# HMC2003_module_SET_RESET.net
KiCad netlist of a schematic drawn in Altium Designer
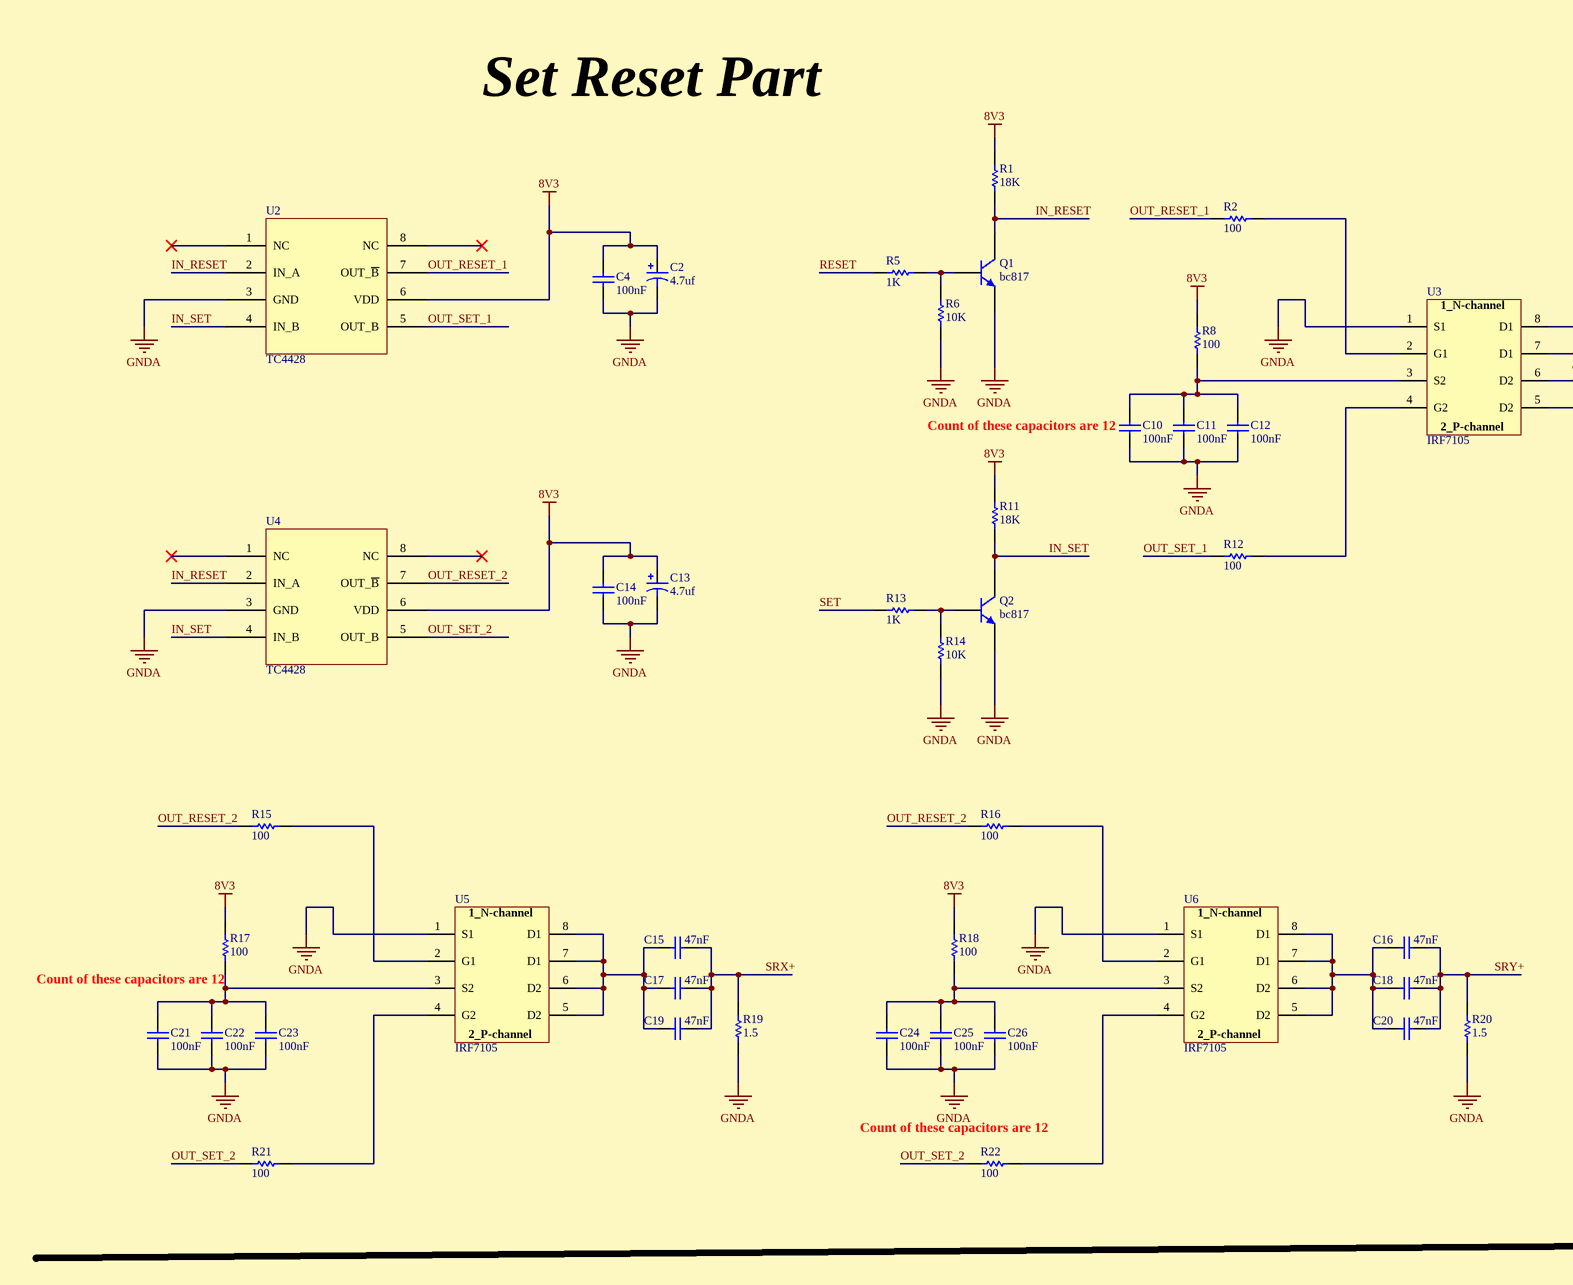
[diagram p0: HMC2003_module_SET_RESET.SchDoc, left]
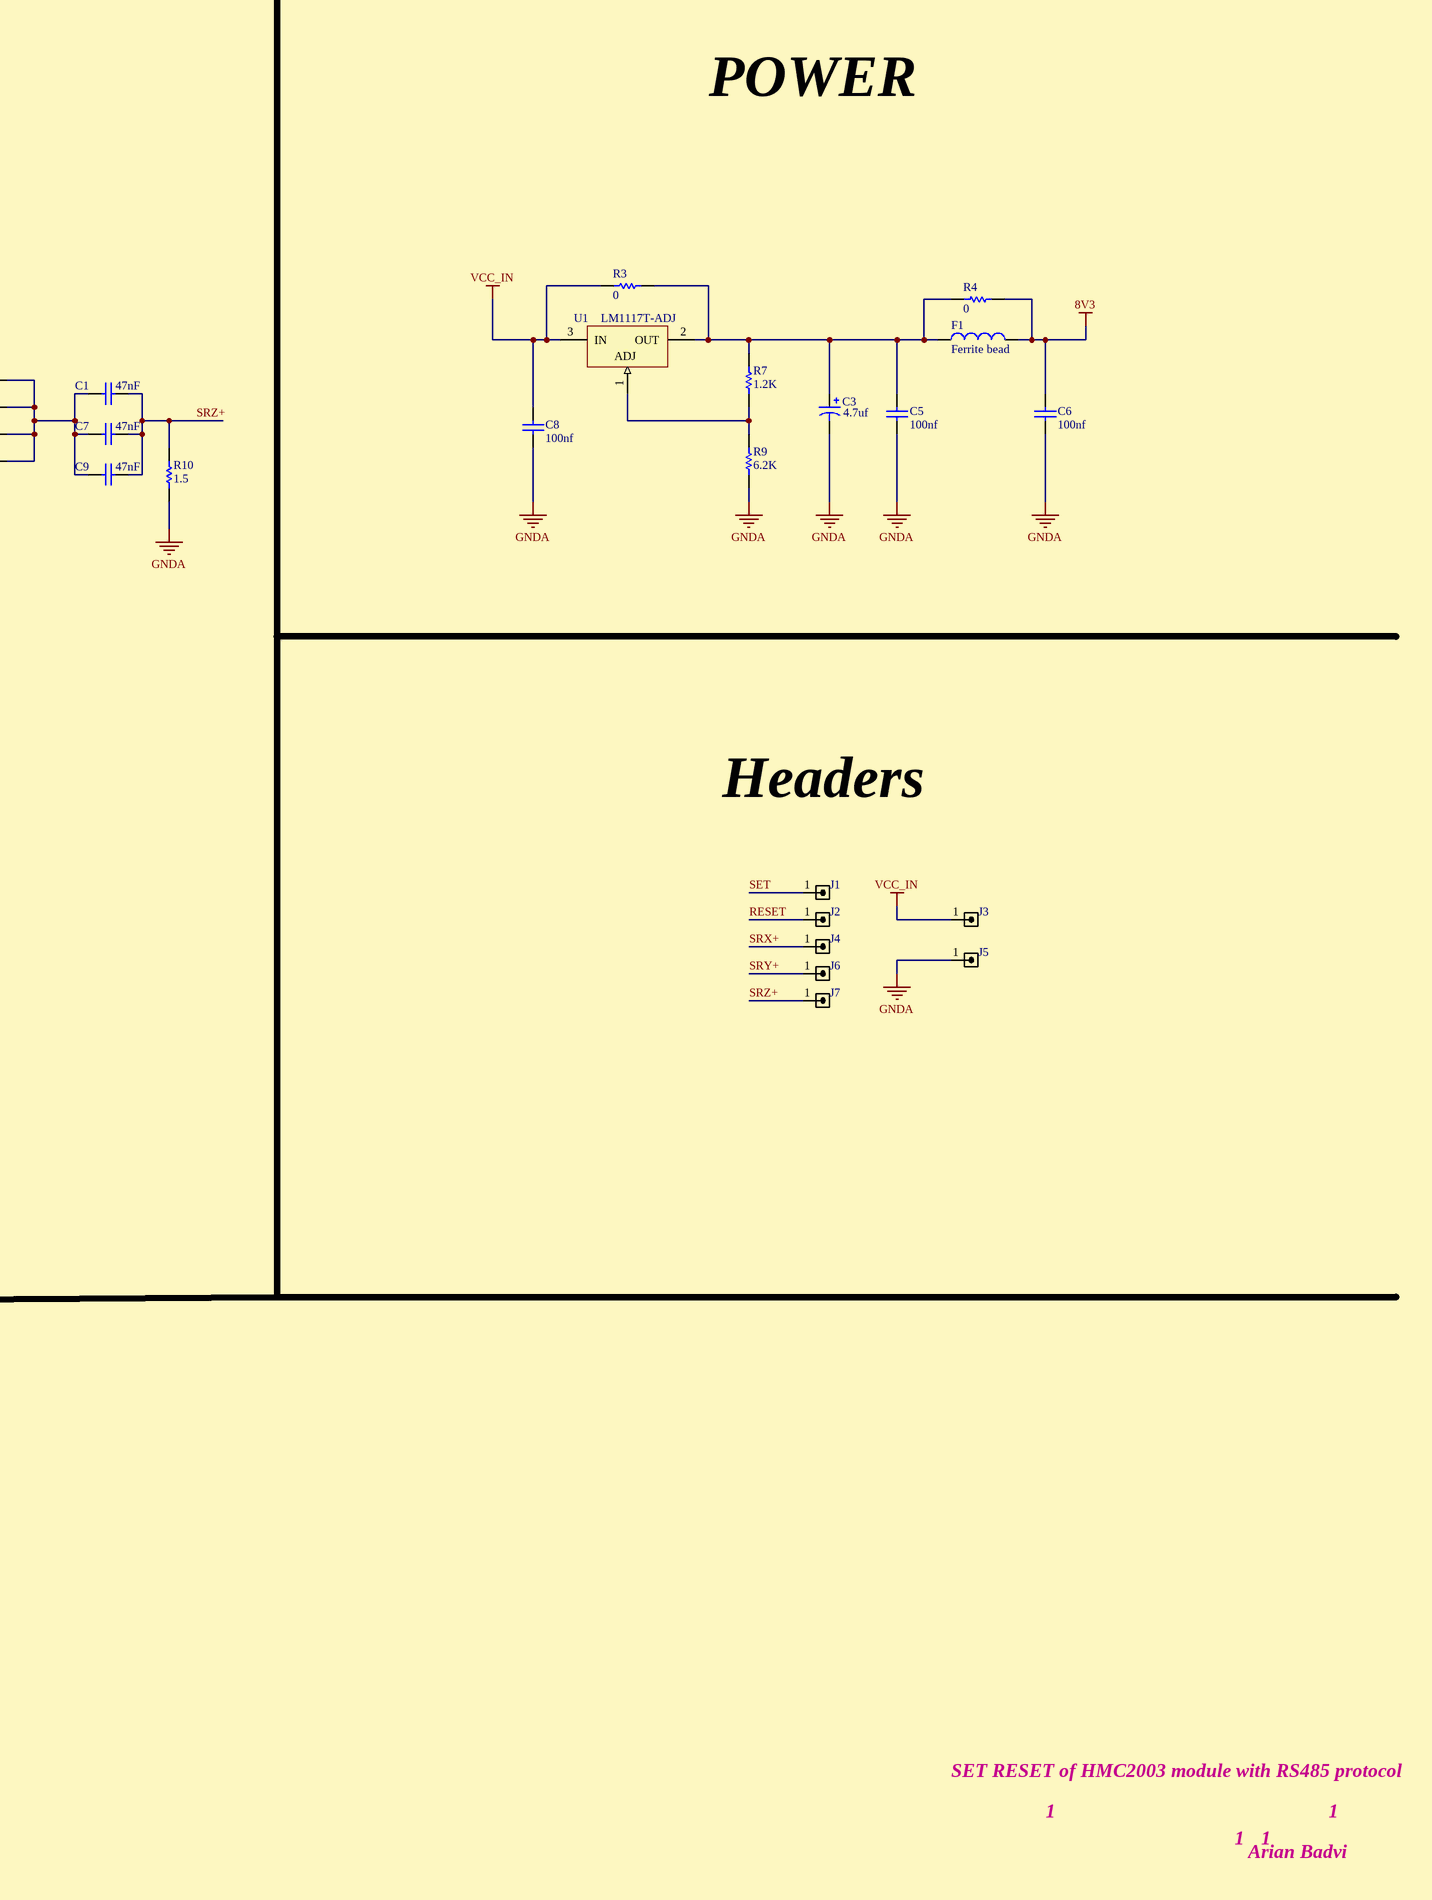
[diagram p1: HMC2003_module_SET_RESET.SchDoc, right]

(export (version "E")
  (design (tool "Eeschema 10.0.6"))
  (components
    (comp (ref "C1")
      (value "47nF")
      (footprint "C1206")
      (description "Capacitor")
      (fields (field (name "PUBLISHER") "Altium Limited"))
      (libsource (lib "Miscellaneous Devices") (part "Cap"))
    )
    (comp (ref "C2")
      (value "4.7uf")
      (footprint "cap_smd_a")
      (description "Polarized Capacitor (Radial)")
      (fields (field (name "PUBLISHER") "Altium Limited"))
      (libsource (lib "Miscellaneous Devices") (part "Cap Pol1"))
    )
    (comp (ref "C3")
      (value "4.7uf")
      (footprint "cap_smd_a")
      (description "Polarized Capacitor (Radial)")
      (fields (field (name "PUBLISHER") "Altium Limited"))
      (libsource (lib "") (part "Cap Pol1_1"))
    )
    (comp (ref "C4")
      (value "100nF")
      (footprint "C0805")
      (description "Capacitor")
      (fields (field (name "PUBLISHER") "Altium Limited"))
      (libsource (lib "") (part "Cap_1"))
    )
    (comp (ref "C5")
      (value "100nf")
      (footprint "C0805")
      (description "Capacitor")
      (fields (field (name "PUBLISHER") "Altium Limited"))
      (libsource (lib "") (part "Cap_1"))
    )
    (comp (ref "C6")
      (value "100nf")
      (footprint "C0805")
      (description "Capacitor")
      (fields (field (name "PUBLISHER") "Altium Limited"))
      (libsource (lib "") (part "Cap_1"))
    )
    (comp (ref "C7")
      (value "47nF")
      (footprint "C1206")
      (description "Capacitor")
      (fields (field (name "PUBLISHER") "Altium Limited"))
      (libsource (lib "Miscellaneous Devices") (part "Cap"))
    )
    (comp (ref "C8")
      (value "100nf")
      (footprint "C0805")
      (description "Capacitor")
      (fields (field (name "PUBLISHER") "Altium Limited"))
      (libsource (lib "") (part "Cap_1"))
    )
    (comp (ref "C9")
      (value "47nF")
      (footprint "C1206")
      (description "Capacitor")
      (fields (field (name "PUBLISHER") "Altium Limited"))
      (libsource (lib "Miscellaneous Devices") (part "Cap"))
    )
    (comp (ref "C10")
      (value "100nF")
      (footprint "C1206")
      (description "Capacitor")
      (fields (field (name "PUBLISHER") "Altium Limited"))
      (libsource (lib "") (part "Cap_1"))
    )
    (comp (ref "C11")
      (value "100nF")
      (footprint "C1206")
      (description "Capacitor")
      (fields (field (name "PUBLISHER") "Altium Limited"))
      (libsource (lib "") (part "Cap_1"))
    )
    (comp (ref "C12")
      (value "100nF")
      (footprint "C1206")
      (description "Capacitor")
      (fields (field (name "PUBLISHER") "Altium Limited"))
      (libsource (lib "") (part "Cap_1"))
    )
    (comp (ref "C13")
      (value "4.7uf")
      (footprint "cap_smd_a")
      (description "Polarized Capacitor (Radial)")
      (fields (field (name "PUBLISHER") "Altium Limited"))
      (libsource (lib "Miscellaneous Devices") (part "Cap Pol1"))
    )
    (comp (ref "C14")
      (value "100nF")
      (footprint "C0805")
      (description "Capacitor")
      (fields (field (name "PUBLISHER") "Altium Limited"))
      (libsource (lib "") (part "Cap_1"))
    )
    (comp (ref "C15")
      (value "47nF")
      (footprint "C1206")
      (description "Capacitor")
      (fields (field (name "PUBLISHER") "Altium Limited"))
      (libsource (lib "Miscellaneous Devices") (part "Cap"))
    )
    (comp (ref "C16")
      (value "47nF")
      (footprint "C1206")
      (description "Capacitor")
      (fields (field (name "PUBLISHER") "Altium Limited"))
      (libsource (lib "Miscellaneous Devices") (part "Cap"))
    )
    (comp (ref "C17")
      (value "47nF")
      (footprint "C1206")
      (description "Capacitor")
      (fields (field (name "PUBLISHER") "Altium Limited"))
      (libsource (lib "Miscellaneous Devices") (part "Cap"))
    )
    (comp (ref "C18")
      (value "47nF")
      (footprint "C1206")
      (description "Capacitor")
      (fields (field (name "PUBLISHER") "Altium Limited"))
      (libsource (lib "Miscellaneous Devices") (part "Cap"))
    )
    (comp (ref "C19")
      (value "47nF")
      (footprint "C1206")
      (description "Capacitor")
      (fields (field (name "PUBLISHER") "Altium Limited"))
      (libsource (lib "Miscellaneous Devices") (part "Cap"))
    )
    (comp (ref "C20")
      (value "47nF")
      (footprint "C1206")
      (description "Capacitor")
      (fields (field (name "PUBLISHER") "Altium Limited"))
      (libsource (lib "Miscellaneous Devices") (part "Cap"))
    )
    (comp (ref "C21")
      (value "100nF")
      (footprint "C1206")
      (description "Capacitor")
      (fields (field (name "PUBLISHER") "Altium Limited"))
      (libsource (lib "") (part "Cap_1"))
    )
    (comp (ref "C22")
      (value "100nF")
      (footprint "C1206")
      (description "Capacitor")
      (fields (field (name "PUBLISHER") "Altium Limited"))
      (libsource (lib "") (part "Cap_1"))
    )
    (comp (ref "C23")
      (value "100nF")
      (footprint "C1206")
      (description "Capacitor")
      (fields (field (name "PUBLISHER") "Altium Limited"))
      (libsource (lib "") (part "Cap_1"))
    )
    (comp (ref "C24")
      (value "100nF")
      (footprint "C1206")
      (description "Capacitor")
      (fields (field (name "PUBLISHER") "Altium Limited"))
      (libsource (lib "") (part "Cap_1"))
    )
    (comp (ref "C25")
      (value "100nF")
      (footprint "C1206")
      (description "Capacitor")
      (fields (field (name "PUBLISHER") "Altium Limited"))
      (libsource (lib "") (part "Cap_1"))
    )
    (comp (ref "C26")
      (value "100nF")
      (footprint "C1206")
      (description "Capacitor")
      (fields (field (name "PUBLISHER") "Altium Limited"))
      (libsource (lib "") (part "Cap_1"))
    )
    (comp (ref "F1")
      (value "Ferrite bead")
      (footprint "0805")
      (description "Ferrite bead, 1206")
      (fields (field (name "PUBLISHER") "Altium Limited"))
      (libsource (lib "Miscellaneous Devices") (part "Inductor"))
    )
    (comp (ref "J1")
      (value "HDRM1")
      (footprint "HDR_M_1")
      (description "CONN, HEADER, Male, pitch: 2.54mm, 1POS")
      (libsource (lib "A7DDS") (part "HDR_M_1"))
    )
    (comp (ref "J2")
      (value "HDRM1")
      (footprint "HDR_M_1")
      (description "CONN, HEADER, Male, pitch: 2.54mm, 1POS")
      (libsource (lib "A7DDS") (part "HDR_M_1"))
    )
    (comp (ref "J3")
      (value "HDRM1")
      (footprint "HDR_M_1")
      (description "CONN, HEADER, Male, pitch: 2.54mm, 1POS")
      (libsource (lib "A7DDS") (part "HDR_M_1"))
    )
    (comp (ref "J4")
      (value "HDRM1")
      (footprint "HDR_M_1")
      (description "CONN, HEADER, Male, pitch: 2.54mm, 1POS")
      (libsource (lib "A7DDS") (part "HDR_M_1"))
    )
    (comp (ref "J5")
      (value "HDRM1")
      (footprint "HDR_M_1")
      (description "CONN, HEADER, Male, pitch: 2.54mm, 1POS")
      (libsource (lib "A7DDS") (part "HDR_M_1"))
    )
    (comp (ref "J6")
      (value "HDRM1")
      (footprint "HDR_M_1")
      (description "CONN, HEADER, Male, pitch: 2.54mm, 1POS")
      (libsource (lib "A7DDS") (part "HDR_M_1"))
    )
    (comp (ref "J7")
      (value "HDRM1")
      (footprint "HDR_M_1")
      (description "CONN, HEADER, Male, pitch: 2.54mm, 1POS")
      (libsource (lib "A7DDS") (part "HDR_M_1"))
    )
    (comp (ref "Q1")
      (value "bc817")
      (footprint "sot-23")
      (description "NPN General Purpose Amplifier")
      (fields (field (name "PUBLISHER") "Altium Limited"))
      (libsource (lib "Miscellaneous Devices") (part "2N3904"))
    )
    (comp (ref "Q2")
      (value "bc817")
      (footprint "sot-23")
      (description "NPN General Purpose Amplifier")
      (fields (field (name "PUBLISHER") "Altium Limited"))
      (libsource (lib "Miscellaneous Devices") (part "2N3904"))
    )
    (comp (ref "R1")
      (value "18K")
      (footprint "0805")
      (description "Resistor")
      (fields (field (name "PUBLISHER") "Altium Limited"))
      (libsource (lib "Miscellaneous Devices") (part "Res1"))
    )
    (comp (ref "R2")
      (value "100")
      (footprint "0805")
      (description "Resistor")
      (fields (field (name "PUBLISHER") "Altium Limited"))
      (libsource (lib "Miscellaneous Devices") (part "Res1"))
    )
    (comp (ref "R3")
      (value "0")
      (footprint "0603")
      (description "Resistor")
      (fields (field (name "PUBLISHER") "Seyed Razi Vesali") (field (name "EMAIL") "razi.vesali@gmail.com"))
      (libsource (lib "resistor1") (part "Resistor"))
    )
    (comp (ref "R4")
      (value "0")
      (footprint "0603")
      (description "Resistor")
      (fields (field (name "PUBLISHER") "Seyed Razi Vesali") (field (name "EMAIL") "razi.vesali@gmail.com"))
      (libsource (lib "resistor1") (part "Resistor"))
    )
    (comp (ref "R5")
      (value "1K")
      (footprint "0805")
      (description "Resistor")
      (fields (field (name "PUBLISHER") "Altium Limited"))
      (libsource (lib "Miscellaneous Devices") (part "Res1"))
    )
    (comp (ref "R6")
      (value "10K")
      (footprint "0805")
      (description "Resistor")
      (fields (field (name "PUBLISHER") "Altium Limited"))
      (libsource (lib "Miscellaneous Devices") (part "Res1"))
    )
    (comp (ref "R7")
      (value "1.2K")
      (footprint "0805")
      (description "Resistor")
      (fields (field (name "PUBLISHER") "Seyed Razi Vesali") (field (name "EMAIL") "razi.vesali@gmail.com"))
      (libsource (lib "resistor1") (part "Resistor"))
    )
    (comp (ref "R8")
      (value "100")
      (footprint "0805")
      (description "Resistor")
      (fields (field (name "PUBLISHER") "Altium Limited"))
      (libsource (lib "Miscellaneous Devices") (part "Res1"))
    )
    (comp (ref "R9")
      (value "6.2K")
      (footprint "0805")
      (description "Resistor")
      (fields (field (name "PUBLISHER") "Seyed Razi Vesali") (field (name "EMAIL") "razi.vesali@gmail.com"))
      (libsource (lib "resistor1") (part "Resistor"))
    )
    (comp (ref "R10")
      (value "1.5")
      (footprint "0805")
      (description "Resistor")
      (fields (field (name "PUBLISHER") "Altium Limited"))
      (libsource (lib "Miscellaneous Devices") (part "Res1"))
    )
    (comp (ref "R11")
      (value "18K")
      (footprint "0805")
      (description "Resistor")
      (fields (field (name "PUBLISHER") "Altium Limited"))
      (libsource (lib "Miscellaneous Devices") (part "Res1"))
    )
    (comp (ref "R12")
      (value "100")
      (footprint "0805")
      (description "Resistor")
      (fields (field (name "PUBLISHER") "Altium Limited"))
      (libsource (lib "Miscellaneous Devices") (part "Res1"))
    )
    (comp (ref "R13")
      (value "1K")
      (footprint "0805")
      (description "Resistor")
      (fields (field (name "PUBLISHER") "Altium Limited"))
      (libsource (lib "Miscellaneous Devices") (part "Res1"))
    )
    (comp (ref "R14")
      (value "10K")
      (footprint "0805")
      (description "Resistor")
      (fields (field (name "PUBLISHER") "Altium Limited"))
      (libsource (lib "Miscellaneous Devices") (part "Res1"))
    )
    (comp (ref "R15")
      (value "100")
      (footprint "0805")
      (description "Resistor")
      (fields (field (name "PUBLISHER") "Altium Limited"))
      (libsource (lib "Miscellaneous Devices") (part "Res1"))
    )
    (comp (ref "R16")
      (value "100")
      (footprint "0805")
      (description "Resistor")
      (fields (field (name "PUBLISHER") "Altium Limited"))
      (libsource (lib "Miscellaneous Devices") (part "Res1"))
    )
    (comp (ref "R17")
      (value "100")
      (footprint "0805")
      (description "Resistor")
      (fields (field (name "PUBLISHER") "Altium Limited"))
      (libsource (lib "Miscellaneous Devices") (part "Res1"))
    )
    (comp (ref "R18")
      (value "100")
      (footprint "0805")
      (description "Resistor")
      (fields (field (name "PUBLISHER") "Altium Limited"))
      (libsource (lib "Miscellaneous Devices") (part "Res1"))
    )
    (comp (ref "R19")
      (value "1.5")
      (footprint "0805")
      (description "Resistor")
      (fields (field (name "PUBLISHER") "Altium Limited"))
      (libsource (lib "Miscellaneous Devices") (part "Res1"))
    )
    (comp (ref "R20")
      (value "1.5")
      (footprint "0805")
      (description "Resistor")
      (fields (field (name "PUBLISHER") "Altium Limited"))
      (libsource (lib "Miscellaneous Devices") (part "Res1"))
    )
    (comp (ref "R21")
      (value "100")
      (footprint "0805")
      (description "Resistor")
      (fields (field (name "PUBLISHER") "Altium Limited"))
      (libsource (lib "Miscellaneous Devices") (part "Res1"))
    )
    (comp (ref "R22")
      (value "100")
      (footprint "0805")
      (description "Resistor")
      (fields (field (name "PUBLISHER") "Altium Limited"))
      (libsource (lib "Miscellaneous Devices") (part "Res1"))
    )
    (comp (ref "U1")
      (value "LM1117T-ADJ")
      (footprint "DPAK")
      (description "800mA Low-Dropout Linear Regulator")
      (fields
        (field (name "MANUFACTURER") "National Semiconductor")
        (field (name "DIGIKEYPARTNUMBER") "LM1117T-ADJ-ND")
        (field (name "PUBLISHER") "Altium Limited")
      )
      (libsource (lib "NSC LDO") (part "LM1117T-ADJ"))
    )
    (comp (ref "U2") (value "TC4428") (footprint "sop8") (libsource (lib "tc4428") (part "TC4428")))
    (comp (ref "U3") (value "IRF7105") (footprint "sop8") (libsource (lib "irf7106") (part "IRF7106")))
    (comp (ref "U4") (value "TC4428") (footprint "sop8") (libsource (lib "tc4428") (part "TC4428")))
    (comp (ref "U5") (value "IRF7105") (footprint "sop8") (libsource (lib "irf7106") (part "IRF7106")))
    (comp (ref "U6") (value "IRF7105") (footprint "sop8") (libsource (lib "irf7106") (part "IRF7106")))
  )
  (nets
    (net (code "1") (name "/IN_RESET") (class "Default")
      (node (ref "Q1") (pin "3") (pinfunction "C_3") (pintype "passive"))
      (node (ref "R1") (pin "1") (pinfunction "1_1") (pintype "passive"))
      (node (ref "U2") (pin "2") (pinfunction "IN_A_2") (pintype "passive"))
      (node (ref "U4") (pin "2") (pinfunction "IN_A_2") (pintype "passive"))
    )
    (net (code "2") (name "/IN_SET") (class "Default")
      (node (ref "Q2") (pin "3") (pinfunction "C_3") (pintype "passive"))
      (node (ref "R11") (pin "1") (pinfunction "1_1") (pintype "passive"))
      (node (ref "U2") (pin "4") (pinfunction "IN_B_4") (pintype "passive"))
      (node (ref "U4") (pin "4") (pinfunction "IN_B_4") (pintype "passive"))
    )
    (net (code "3") (name "/OUT_RESET_1") (class "Default")
      (node (ref "R2") (pin "2") (pinfunction "2_2") (pintype "passive"))
      (node (ref "U2") (pin "7") (pinfunction "OUT_~{B}_7") (pintype "passive"))
    )
    (net (code "4") (name "/OUT_RESET_2") (class "Default")
      (node (ref "R15") (pin "2") (pinfunction "2_2") (pintype "passive"))
      (node (ref "R16") (pin "2") (pinfunction "2_2") (pintype "passive"))
      (node (ref "U4") (pin "7") (pinfunction "OUT_~{B}_7") (pintype "passive"))
    )
    (net (code "5") (name "/OUT_SET_1") (class "Default")
      (node (ref "R12") (pin "2") (pinfunction "2_2") (pintype "passive"))
      (node (ref "U2") (pin "5") (pinfunction "OUT_B_5") (pintype "passive"))
    )
    (net (code "6") (name "/OUT_SET_2") (class "Default")
      (node (ref "R21") (pin "2") (pinfunction "2_2") (pintype "passive"))
      (node (ref "R22") (pin "2") (pinfunction "2_2") (pintype "passive"))
      (node (ref "U4") (pin "5") (pinfunction "OUT_B_5") (pintype "passive"))
    )
    (net (code "7") (name "/RESET") (class "Default")
      (node (ref "J2") (pin "1") (pinfunction "1_1") (pintype "passive"))
      (node (ref "R5") (pin "1") (pinfunction "1_1") (pintype "passive"))
    )
    (net (code "8") (name "/SET") (class "Default")
      (node (ref "J1") (pin "1") (pinfunction "1_1") (pintype "passive"))
      (node (ref "R13") (pin "1") (pinfunction "1_1") (pintype "passive"))
    )
    (net (code "9") (name "/SRX+") (class "Default")
      (node (ref "C15") (pin "2") (pinfunction "2_2") (pintype "passive"))
      (node (ref "C17") (pin "2") (pinfunction "2_2") (pintype "passive"))
      (node (ref "C19") (pin "2") (pinfunction "2_2") (pintype "passive"))
      (node (ref "J4") (pin "1") (pinfunction "1_1") (pintype "passive"))
      (node (ref "R19") (pin "1") (pinfunction "1_1") (pintype "passive"))
    )
    (net (code "10") (name "/SRY+") (class "Default")
      (node (ref "C16") (pin "2") (pinfunction "2_2") (pintype "passive"))
      (node (ref "C18") (pin "2") (pinfunction "2_2") (pintype "passive"))
      (node (ref "C20") (pin "2") (pinfunction "2_2") (pintype "passive"))
      (node (ref "J6") (pin "1") (pinfunction "1_1") (pintype "passive"))
      (node (ref "R20") (pin "1") (pinfunction "1_1") (pintype "passive"))
    )
    (net (code "11") (name "/SRZ+") (class "Default")
      (node (ref "C1") (pin "2") (pinfunction "2_2") (pintype "passive"))
      (node (ref "C7") (pin "2") (pinfunction "2_2") (pintype "passive"))
      (node (ref "C9") (pin "2") (pinfunction "2_2") (pintype "passive"))
      (node (ref "J7") (pin "1") (pinfunction "1_1") (pintype "passive"))
      (node (ref "R10") (pin "1") (pinfunction "1_1") (pintype "passive"))
    )
    (net (code "12") (name "8V3") (class "Default")
      (node (ref "C13") (pin "1") (pinfunction "1_1") (pintype "passive"))
      (node (ref "C14") (pin "1") (pinfunction "1_1") (pintype "passive"))
      (node (ref "C2") (pin "1") (pinfunction "1_1") (pintype "passive"))
      (node (ref "C4") (pin "1") (pinfunction "1_1") (pintype "passive"))
      (node (ref "C6") (pin "2") (pinfunction "2_2") (pintype "passive"))
      (node (ref "F1") (pin "2") (pinfunction "2_2") (pintype "passive"))
      (node (ref "R1") (pin "2") (pinfunction "2_2") (pintype "passive"))
      (node (ref "R11") (pin "2") (pinfunction "2_2") (pintype "passive"))
      (node (ref "R17") (pin "1") (pinfunction "1_1") (pintype "passive"))
      (node (ref "R18") (pin "1") (pinfunction "1_1") (pintype "passive"))
      (node (ref "R4") (pin "1") (pinfunction "1_1") (pintype "passive"))
      (node (ref "R8") (pin "1") (pinfunction "1_1") (pintype "passive"))
      (node (ref "U2") (pin "6") (pinfunction "VDD_6") (pintype "passive"))
      (node (ref "U4") (pin "6") (pinfunction "VDD_6") (pintype "passive"))
    )
    (net (code "13") (name "GNDA") (class "Default")
      (node (ref "C10") (pin "2") (pinfunction "2_2") (pintype "passive"))
      (node (ref "C11") (pin "2") (pinfunction "2_2") (pintype "passive"))
      (node (ref "C12") (pin "2") (pinfunction "2_2") (pintype "passive"))
      (node (ref "C13") (pin "2") (pinfunction "2_2") (pintype "passive"))
      (node (ref "C14") (pin "2") (pinfunction "2_2") (pintype "passive"))
      (node (ref "C2") (pin "2") (pinfunction "2_2") (pintype "passive"))
      (node (ref "C21") (pin "2") (pinfunction "2_2") (pintype "passive"))
      (node (ref "C22") (pin "2") (pinfunction "2_2") (pintype "passive"))
      (node (ref "C23") (pin "2") (pinfunction "2_2") (pintype "passive"))
      (node (ref "C24") (pin "2") (pinfunction "2_2") (pintype "passive"))
      (node (ref "C25") (pin "2") (pinfunction "2_2") (pintype "passive"))
      (node (ref "C26") (pin "2") (pinfunction "2_2") (pintype "passive"))
      (node (ref "C3") (pin "2") (pinfunction "2_2") (pintype "passive"))
      (node (ref "C4") (pin "2") (pinfunction "2_2") (pintype "passive"))
      (node (ref "C5") (pin "1") (pinfunction "1_1") (pintype "passive"))
      (node (ref "C6") (pin "1") (pinfunction "1_1") (pintype "passive"))
      (node (ref "C8") (pin "1") (pinfunction "1_1") (pintype "passive"))
      (node (ref "J5") (pin "1") (pinfunction "1_1") (pintype "passive"))
      (node (ref "Q1") (pin "2") (pinfunction "E_2") (pintype "passive"))
      (node (ref "Q2") (pin "2") (pinfunction "E_2") (pintype "passive"))
      (node (ref "R10") (pin "2") (pinfunction "2_2") (pintype "passive"))
      (node (ref "R14") (pin "1") (pinfunction "1_1") (pintype "passive"))
      (node (ref "R19") (pin "2") (pinfunction "2_2") (pintype "passive"))
      (node (ref "R20") (pin "2") (pinfunction "2_2") (pintype "passive"))
      (node (ref "R6") (pin "1") (pinfunction "1_1") (pintype "passive"))
      (node (ref "R9") (pin "1") (pinfunction "1_1") (pintype "passive"))
      (node (ref "U2") (pin "3") (pinfunction "GND_3") (pintype "passive"))
      (node (ref "U3") (pin "1") (pinfunction "S1_1") (pintype "passive"))
      (node (ref "U4") (pin "3") (pinfunction "GND_3") (pintype "passive"))
      (node (ref "U5") (pin "1") (pinfunction "S1_1") (pintype "passive"))
      (node (ref "U6") (pin "1") (pinfunction "S1_1") (pintype "passive"))
    )
    (net (code "14") (name "Net-(C1-Pad1)") (class "Default")
      (node (ref "C1") (pin "1") (pinfunction "1_1") (pintype "passive"))
      (node (ref "C7") (pin "1") (pinfunction "1_1") (pintype "passive"))
      (node (ref "C9") (pin "1") (pinfunction "1_1") (pintype "passive"))
      (node (ref "U3") (pin "5") (pinfunction "D2_5") (pintype "passive"))
      (node (ref "U3") (pin "6") (pinfunction "D2_6") (pintype "passive"))
      (node (ref "U3") (pin "7") (pinfunction "D1_7") (pintype "passive"))
      (node (ref "U3") (pin "8") (pinfunction "D1_8") (pintype "passive"))
    )
    (net (code "15") (name "Net-(C15-Pad1)") (class "Default")
      (node (ref "C15") (pin "1") (pinfunction "1_1") (pintype "passive"))
      (node (ref "C17") (pin "1") (pinfunction "1_1") (pintype "passive"))
      (node (ref "C19") (pin "1") (pinfunction "1_1") (pintype "passive"))
      (node (ref "U5") (pin "5") (pinfunction "D2_5") (pintype "passive"))
      (node (ref "U5") (pin "6") (pinfunction "D2_6") (pintype "passive"))
      (node (ref "U5") (pin "7") (pinfunction "D1_7") (pintype "passive"))
      (node (ref "U5") (pin "8") (pinfunction "D1_8") (pintype "passive"))
    )
    (net (code "16") (name "Net-(C16-Pad1)") (class "Default")
      (node (ref "C16") (pin "1") (pinfunction "1_1") (pintype "passive"))
      (node (ref "C18") (pin "1") (pinfunction "1_1") (pintype "passive"))
      (node (ref "C20") (pin "1") (pinfunction "1_1") (pintype "passive"))
      (node (ref "U6") (pin "5") (pinfunction "D2_5") (pintype "passive"))
      (node (ref "U6") (pin "6") (pinfunction "D2_6") (pintype "passive"))
      (node (ref "U6") (pin "7") (pinfunction "D1_7") (pintype "passive"))
      (node (ref "U6") (pin "8") (pinfunction "D1_8") (pintype "passive"))
    )
    (net (code "17") (name "Net-(Q1-B)") (class "Default")
      (node (ref "Q1") (pin "1") (pinfunction "B_1") (pintype "passive"))
      (node (ref "R5") (pin "2") (pinfunction "2_2") (pintype "passive"))
      (node (ref "R6") (pin "2") (pinfunction "2_2") (pintype "passive"))
    )
    (net (code "18") (name "Net-(Q2-B)") (class "Default")
      (node (ref "Q2") (pin "1") (pinfunction "B_1") (pintype "passive"))
      (node (ref "R13") (pin "2") (pinfunction "2_2") (pintype "passive"))
      (node (ref "R14") (pin "2") (pinfunction "2_2") (pintype "passive"))
    )
    (net (code "19") (name "Net-(U1-ADJ)") (class "Default")
      (node (ref "R7") (pin "1") (pinfunction "1_1") (pintype "passive"))
      (node (ref "R9") (pin "2") (pinfunction "2_2") (pintype "passive"))
      (node (ref "U1") (pin "1") (pinfunction "ADJ_1") (pintype "input"))
    )
    (net (code "20") (name "Net-(U1-OUT)") (class "Default")
      (node (ref "C3") (pin "1") (pinfunction "1_1") (pintype "passive"))
      (node (ref "C5") (pin "2") (pinfunction "2_2") (pintype "passive"))
      (node (ref "F1") (pin "1") (pinfunction "1_1") (pintype "passive"))
      (node (ref "R3") (pin "1") (pinfunction "1_1") (pintype "passive"))
      (node (ref "R4") (pin "2") (pinfunction "2_2") (pintype "passive"))
      (node (ref "R7") (pin "2") (pinfunction "2_2") (pintype "passive"))
      (node (ref "U1") (pin "2") (pinfunction "OUT_2") (pintype "power_in"))
    )
    (net (code "21") (name "Net-(U3-G1)") (class "Default")
      (node (ref "R2") (pin "1") (pinfunction "1_1") (pintype "passive"))
      (node (ref "U3") (pin "2") (pinfunction "G1_2") (pintype "passive"))
    )
    (net (code "22") (name "Net-(U3-G2)") (class "Default")
      (node (ref "R12") (pin "1") (pinfunction "1_1") (pintype "passive"))
      (node (ref "U3") (pin "4") (pinfunction "G2_4") (pintype "passive"))
    )
    (net (code "23") (name "Net-(U3-S2)") (class "Default")
      (node (ref "C10") (pin "1") (pinfunction "1_1") (pintype "passive"))
      (node (ref "C11") (pin "1") (pinfunction "1_1") (pintype "passive"))
      (node (ref "C12") (pin "1") (pinfunction "1_1") (pintype "passive"))
      (node (ref "R8") (pin "2") (pinfunction "2_2") (pintype "passive"))
      (node (ref "U3") (pin "3") (pinfunction "S2_3") (pintype "passive"))
    )
    (net (code "24") (name "Net-(U5-G1)") (class "Default")
      (node (ref "R15") (pin "1") (pinfunction "1_1") (pintype "passive"))
      (node (ref "U5") (pin "2") (pinfunction "G1_2") (pintype "passive"))
    )
    (net (code "25") (name "Net-(U5-G2)") (class "Default")
      (node (ref "R21") (pin "1") (pinfunction "1_1") (pintype "passive"))
      (node (ref "U5") (pin "4") (pinfunction "G2_4") (pintype "passive"))
    )
    (net (code "26") (name "Net-(U5-S2)") (class "Default")
      (node (ref "C21") (pin "1") (pinfunction "1_1") (pintype "passive"))
      (node (ref "C22") (pin "1") (pinfunction "1_1") (pintype "passive"))
      (node (ref "C23") (pin "1") (pinfunction "1_1") (pintype "passive"))
      (node (ref "R17") (pin "2") (pinfunction "2_2") (pintype "passive"))
      (node (ref "U5") (pin "3") (pinfunction "S2_3") (pintype "passive"))
    )
    (net (code "27") (name "Net-(U6-G1)") (class "Default")
      (node (ref "R16") (pin "1") (pinfunction "1_1") (pintype "passive"))
      (node (ref "U6") (pin "2") (pinfunction "G1_2") (pintype "passive"))
    )
    (net (code "28") (name "Net-(U6-G2)") (class "Default")
      (node (ref "R22") (pin "1") (pinfunction "1_1") (pintype "passive"))
      (node (ref "U6") (pin "4") (pinfunction "G2_4") (pintype "passive"))
    )
    (net (code "29") (name "Net-(U6-S2)") (class "Default")
      (node (ref "C24") (pin "1") (pinfunction "1_1") (pintype "passive"))
      (node (ref "C25") (pin "1") (pinfunction "1_1") (pintype "passive"))
      (node (ref "C26") (pin "1") (pinfunction "1_1") (pintype "passive"))
      (node (ref "R18") (pin "2") (pinfunction "2_2") (pintype "passive"))
      (node (ref "U6") (pin "3") (pinfunction "S2_3") (pintype "passive"))
    )
    (net (code "30") (name "VCC_IN") (class "Default")
      (node (ref "C8") (pin "2") (pinfunction "2_2") (pintype "passive"))
      (node (ref "J3") (pin "1") (pinfunction "1_1") (pintype "passive"))
      (node (ref "R3") (pin "2") (pinfunction "2_2") (pintype "passive"))
      (node (ref "U1") (pin "3") (pinfunction "IN_3") (pintype "power_in"))
    )
    (net (code "31") (name "unconnected-(U2-NC-Pad1)") (class "Default")
      (node (ref "U2") (pin "1") (pinfunction "NC_1") (pintype "passive+no_connect"))
    )
    (net (code "32") (name "unconnected-(U2-NC-Pad8)") (class "Default")
      (node (ref "U2") (pin "8") (pinfunction "NC_8") (pintype "passive+no_connect"))
    )
    (net (code "33") (name "unconnected-(U4-NC-Pad1)") (class "Default")
      (node (ref "U4") (pin "1") (pinfunction "NC_1") (pintype "passive+no_connect"))
    )
    (net (code "34") (name "unconnected-(U4-NC-Pad8)") (class "Default")
      (node (ref "U4") (pin "8") (pinfunction "NC_8") (pintype "passive+no_connect"))
    )
  )
)
